# RPiPwrCtrlBrd.net
KiCad netlist of a schematic drawn in EAGLE
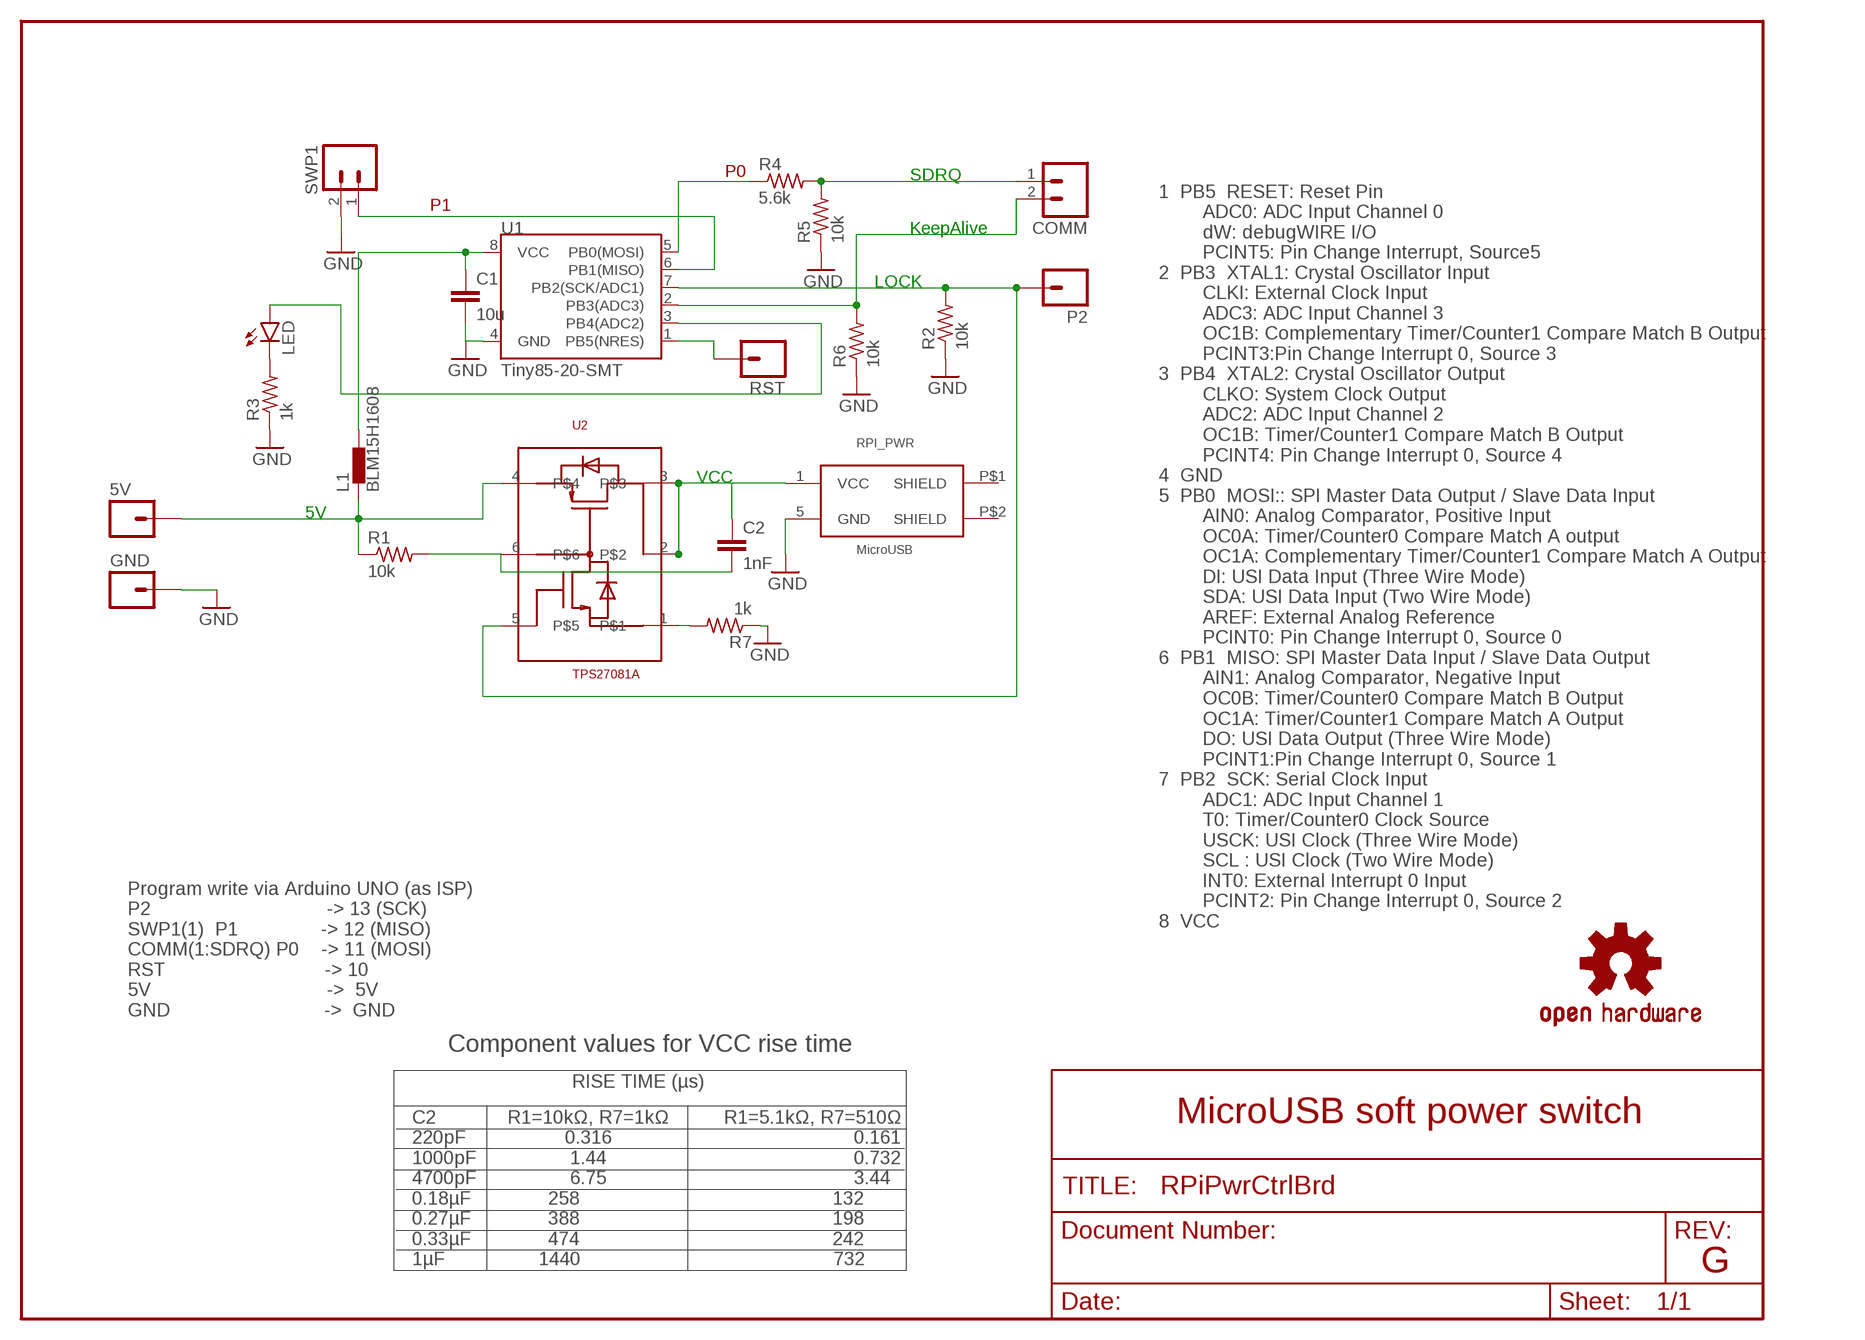
[diagram p0: schematic, sheet 1]

(export (version "E")
  (design (tool "Eeschema 10.0.6"))
  (components
    (comp (ref "5V")
      (value "M01PTH")
      (footprint "eagle-import:1X01")
      (libsource (lib "eagle-import") (part "M01PTH"))
    )
    (comp (ref "C1")
      (value "10u")
      (footprint "eagle-import:1608")
      (libsource (lib "eagle-import") (part "CAP1608"))
    )
    (comp (ref "C2")
      (value "1nF")
      (footprint "eagle-import:1608")
      (libsource (lib "eagle-import") (part "CAP1608"))
    )
    (comp (ref "COMM")
      (value "M02PTH")
      (footprint "eagle-import:1X02")
      (libsource (lib "eagle-import") (part "M02PTH"))
    )
    (comp (ref "GND")
      (value "M01PTH")
      (footprint "eagle-import:1X01")
      (libsource (lib "eagle-import") (part "M01PTH"))
    )
    (comp (ref "L1")
      (value "BLM15H1608")
      (footprint "eagle-import:1608")
      (libsource (lib "eagle-import") (part "BLM15H1608"))
    )
    (comp (ref "LED")
      (value "LED0603")
      (footprint "eagle-import:LED-0603")
      (libsource (lib "eagle-import") (part "LED0603"))
    )
    (comp (ref "P2")
      (value "M01PTH")
      (footprint "eagle-import:1X01")
      (libsource (lib "eagle-import") (part "M01PTH"))
    )
    (comp (ref "R1")
      (value "10k")
      (footprint "eagle-import:1608")
      (libsource (lib "eagle-import") (part "R-US_1608"))
    )
    (comp (ref "R2")
      (value "10k")
      (footprint "eagle-import:1608")
      (libsource (lib "eagle-import") (part "R-US_1608"))
    )
    (comp (ref "R3")
      (value "1k")
      (footprint "eagle-import:1608")
      (libsource (lib "eagle-import") (part "R-US_1608"))
    )
    (comp (ref "R4")
      (value "5.6k")
      (footprint "eagle-import:1608")
      (libsource (lib "eagle-import") (part "R-US_1608"))
    )
    (comp (ref "R5")
      (value "10k")
      (footprint "eagle-import:1608")
      (libsource (lib "eagle-import") (part "R-US_1608"))
    )
    (comp (ref "R6")
      (value "10k")
      (footprint "eagle-import:1608")
      (libsource (lib "eagle-import") (part "R-US_1608"))
    )
    (comp (ref "R7")
      (value "1k")
      (footprint "eagle-import:1608")
      (libsource (lib "eagle-import") (part "R-US_1608"))
    )
    (comp (ref "RPI_PWR")
      (value "MicroUSB")
      (footprint "eagle-import:MICRO-B-THPWR")
      (libsource (lib "eagle-import") (part "USB_MICROB_PLUG_PWR"))
    )
    (comp (ref "RST")
      (value "M01PTH")
      (footprint "eagle-import:1X01")
      (libsource (lib "eagle-import") (part "M01PTH"))
    )
    (comp (ref "SWP1")
      (value "M02PTH")
      (footprint "eagle-import:1X02")
      (libsource (lib "eagle-import") (part "M02PTH"))
    )
    (comp (ref "U$1")
      (value "OSHW-LOGOS")
      (footprint "eagle-import:OSHW-LOGO-S")
      (libsource (lib "eagle-import") (part "OSHW-LOGOS"))
    )
    (comp (ref "U1")
      (value "Tiny85-20-SMT")
      (footprint "eagle-import:SO08-EIAJ")
      (libsource (lib "eagle-import") (part "ATTINY45TINY85-20-SMT"))
    )
    (comp (ref "U2")
      (value "TPS27081A")
      (footprint "eagle-import:SOT23-6")
      (libsource (lib "eagle-import") (part "TPS27081A"))
    )
  )
  (nets
    (net (code "1") (name "GND") (class "Default")
      (node (ref "C1") (pin "P$2") (pinfunction "2_P$2") (pintype "passive"))
      (node (ref "GND") (pin "1") (pinfunction "1_1") (pintype "passive"))
      (node (ref "R2") (pin "P$1") (pinfunction "1_P$1") (pintype "passive"))
      (node (ref "R3") (pin "P$1") (pinfunction "1_P$1") (pintype "passive"))
      (node (ref "R5") (pin "P$1") (pinfunction "1_P$1") (pintype "passive"))
      (node (ref "R6") (pin "P$1") (pinfunction "1_P$1") (pintype "passive"))
      (node (ref "R7") (pin "P$1") (pinfunction "1_P$1") (pintype "passive"))
      (node (ref "RPI_PWR") (pin "5") (pinfunction "GND_5") (pintype "power_in"))
      (node (ref "SWP1") (pin "2") (pinfunction "2_2") (pintype "passive"))
      (node (ref "U1") (pin "4") (pinfunction "GND_4") (pintype "bidirectional"))
    )
    (net (code "2") (name "Net-(C1-1)") (class "Default")
      (node (ref "C1") (pin "P$1") (pinfunction "1_P$1") (pintype "passive"))
      (node (ref "L1") (pin "P$2") (pinfunction "2_P$2") (pintype "passive"))
      (node (ref "U1") (pin "8") (pinfunction "VCC_8") (pintype "bidirectional"))
    )
    (net (code "3") (name "Net-(C2-1)") (class "Default")
      (node (ref "C2") (pin "P$1") (pinfunction "1_P$1") (pintype "passive"))
      (node (ref "RPI_PWR") (pin "1") (pinfunction "VCC_1") (pintype "power_in"))
      (node (ref "U2") (pin "2") (pinfunction "P$2_2") (pintype "output"))
      (node (ref "U2") (pin "3") (pinfunction "P$3_3") (pintype "output"))
    )
    (net (code "4") (name "Net-(C2-2)") (class "Default")
      (node (ref "C2") (pin "P$2") (pinfunction "2_P$2") (pintype "passive"))
      (node (ref "R1") (pin "P$2") (pinfunction "2_P$2") (pintype "passive"))
      (node (ref "U2") (pin "6") (pinfunction "P$6_6") (pintype "bidirectional"))
    )
    (net (code "5") (name "Net-(L1-1)") (class "Default")
      (node (ref "5V") (pin "1") (pinfunction "1_1") (pintype "passive"))
      (node (ref "L1") (pin "P$1") (pinfunction "1_P$1") (pintype "passive"))
      (node (ref "R1") (pin "P$1") (pinfunction "1_P$1") (pintype "passive"))
      (node (ref "U2") (pin "4") (pinfunction "P$4_4") (pintype "power_in"))
    )
    (net (code "6") (name "Net-(R2-2)") (class "Default")
      (node (ref "P2") (pin "1") (pinfunction "1_1") (pintype "passive"))
      (node (ref "R2") (pin "P$2") (pinfunction "2_P$2") (pintype "passive"))
      (node (ref "U1") (pin "7") (pinfunction "PB2(SCK/ADC1)_7") (pintype "bidirectional"))
      (node (ref "U2") (pin "5") (pinfunction "P$5_5") (pintype "input"))
    )
    (net (code "7") (name "Net-(R3-2)") (class "Default")
      (node (ref "LED") (pin "C") (pinfunction "C_C") (pintype "passive"))
      (node (ref "R3") (pin "P$2") (pinfunction "2_P$2") (pintype "passive"))
    )
    (net (code "8") (name "Net-(R4-1)") (class "Default")
      (node (ref "R4") (pin "P$1") (pinfunction "1_P$1") (pintype "passive"))
      (node (ref "U1") (pin "5") (pinfunction "PB0(MOSI)_5") (pintype "bidirectional"))
    )
    (net (code "9") (name "Net-(R4-2)") (class "Default")
      (node (ref "COMM") (pin "1") (pinfunction "1_1") (pintype "passive"))
      (node (ref "R4") (pin "P$2") (pinfunction "2_P$2") (pintype "passive"))
      (node (ref "R5") (pin "P$2") (pinfunction "2_P$2") (pintype "passive"))
    )
    (net (code "10") (name "Net-(R6-2)") (class "Default")
      (node (ref "COMM") (pin "2") (pinfunction "2_2") (pintype "passive"))
      (node (ref "R6") (pin "P$2") (pinfunction "2_P$2") (pintype "passive"))
      (node (ref "U1") (pin "2") (pinfunction "PB3(ADC3)_2") (pintype "bidirectional"))
    )
    (net (code "11") (name "Net-(R7-2)") (class "Default")
      (node (ref "R7") (pin "P$2") (pinfunction "2_P$2") (pintype "passive"))
      (node (ref "U2") (pin "1") (pinfunction "P$1_1") (pintype "bidirectional"))
    )
    (net (code "12") (name "Net-(U1-PB1(MISO))") (class "Default")
      (node (ref "SWP1") (pin "1") (pinfunction "1_1") (pintype "passive"))
      (node (ref "U1") (pin "6") (pinfunction "PB1(MISO)_6") (pintype "bidirectional"))
    )
    (net (code "13") (name "Net-(U1-PB4(ADC2))") (class "Default")
      (node (ref "LED") (pin "A") (pinfunction "A_A") (pintype "passive"))
      (node (ref "U1") (pin "3") (pinfunction "PB4(ADC2)_3") (pintype "bidirectional"))
    )
    (net (code "14") (name "Net-(U1-PB5(NRES))") (class "Default")
      (node (ref "RST") (pin "1") (pinfunction "1_1") (pintype "passive"))
      (node (ref "U1") (pin "1") (pinfunction "PB5(NRES)_1") (pintype "bidirectional"))
    )
    (net (code "15") (name "unconnected-(RPI_PWR-SHIELD-PadP$1)") (class "Default")
      (node (ref "RPI_PWR") (pin "P$1") (pinfunction "SHIELD_P$1") (pintype "bidirectional"))
    )
    (net (code "16") (name "unconnected-(RPI_PWR-SHIELD-PadP$2)") (class "Default")
      (node (ref "RPI_PWR") (pin "P$2") (pinfunction "SHIELD_P$2") (pintype "bidirectional"))
    )
  )
)
